# design.net
KiCad netlist of a schematic drawn in Altium Designer
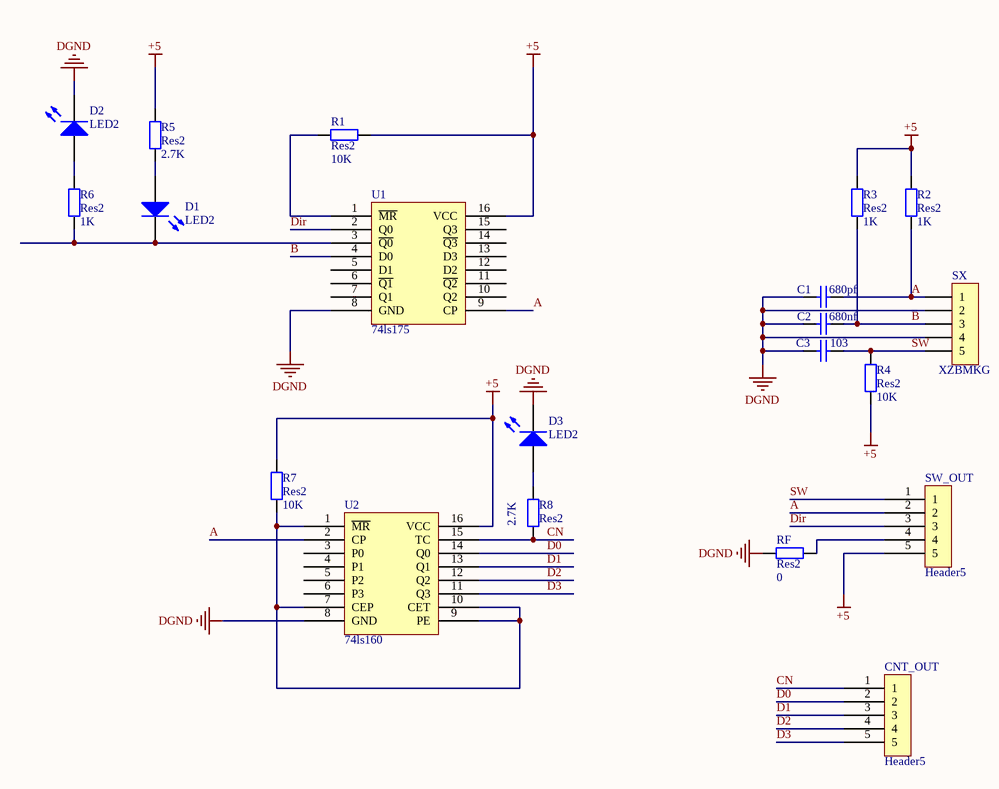
[diagram p0: 正交解码.SchDoc]

(export (version "E")
  (design (tool "Eeschema 10.0.6"))
  (components
    (comp (ref "C1")
      (value "680pf")
      (footprint "0805C")
      (description "Capacitor")
      (fields (field (name "Comment") "104") (field (name "PUBLISHER") "Altium Limited"))
      (libsource (lib "altium-import") (part "root_0_Cap_"))
    )
    (comp (ref "C2")
      (value "680nf")
      (footprint "0805C")
      (description "Capacitor")
      (fields (field (name "Comment") "104") (field (name "PUBLISHER") "Altium Limited"))
      (libsource (lib "altium-import") (part "root_0_Cap_"))
    )
    (comp (ref "C3")
      (value "103")
      (footprint "0805C")
      (description "Capacitor")
      (fields (field (name "Comment") "104") (field (name "PUBLISHER") "Altium Limited"))
      (libsource (lib "altium-import") (part "root_0_Cap_"))
    )
    (comp (ref "CNT_OUT") (value "Header5") (footprint "HDR1X5") (libsource (lib "GDT") (part "Header5")))
    (comp (ref "D1")
      (value "LED2")
      (footprint "LED_0805")
      (description "Typical RED, GREEN, YELLOW, AMBER GaAs LED")
      (fields (field (name "PUBLISHER") "Altium Limited"))
      (libsource (lib "Miscellaneous Devices") (part "LED2"))
    )
    (comp (ref "D2")
      (value "LED2")
      (footprint "LED_0805")
      (description "Typical RED, GREEN, YELLOW, AMBER GaAs LED")
      (fields (field (name "PUBLISHER") "Altium Limited"))
      (libsource (lib "Miscellaneous Devices") (part "LED2"))
    )
    (comp (ref "D3")
      (value "LED2")
      (footprint "LED_0805")
      (description "Typical RED, GREEN, YELLOW, AMBER GaAs LED")
      (fields (field (name "PUBLISHER") "Altium Limited"))
      (libsource (lib "Miscellaneous Devices") (part "LED2"))
    )
    (comp (ref "R1")
      (value "Res2")
      (footprint "0805")
      (description "Resistor")
      (fields (field (name "ALTIUM_VALUE") "10K") (field (name "PUBLISHER") "Altium Limited"))
      (libsource (lib "") (part "Res2_2"))
    )
    (comp (ref "R2")
      (value "Res2")
      (footprint "0805")
      (description "Resistor")
      (fields (field (name "ALTIUM_VALUE") "1K") (field (name "PUBLISHER") "Altium Limited"))
      (libsource (lib "") (part "Res2_1"))
    )
    (comp (ref "R3")
      (value "Res2")
      (footprint "0805")
      (description "Resistor")
      (fields (field (name "ALTIUM_VALUE") "1K") (field (name "PUBLISHER") "Altium Limited"))
      (libsource (lib "") (part "Res2_1"))
    )
    (comp (ref "R4")
      (value "Res2")
      (footprint "0805")
      (description "Resistor")
      (fields (field (name "ALTIUM_VALUE") "10K") (field (name "PUBLISHER") "Altium Limited"))
      (libsource (lib "") (part "Res2_1"))
    )
    (comp (ref "R5")
      (value "Res2")
      (footprint "0805")
      (description "Resistor")
      (fields (field (name "ALTIUM_VALUE") "2.7K") (field (name "PUBLISHER") "Altium Limited"))
      (libsource (lib "Miscellaneous Devices") (part "Res2"))
    )
    (comp (ref "R6")
      (value "Res2")
      (footprint "0805")
      (description "Resistor")
      (fields (field (name "ALTIUM_VALUE") "1K") (field (name "PUBLISHER") "Altium Limited"))
      (libsource (lib "") (part "Res2_1"))
    )
    (comp (ref "R7")
      (value "Res2")
      (footprint "0805")
      (description "Resistor")
      (fields (field (name "ALTIUM_VALUE") "10K") (field (name "PUBLISHER") "Altium Limited"))
      (libsource (lib "") (part "Res2_1"))
    )
    (comp (ref "R8")
      (value "Res2")
      (footprint "0805")
      (description "Resistor")
      (fields (field (name "ALTIUM_VALUE") "2.7K") (field (name "PUBLISHER") "Altium Limited"))
      (libsource (lib "") (part "Res2_1"))
    )
    (comp (ref "RF")
      (value "Res2")
      (footprint "0805")
      (description "Resistor")
      (fields (field (name "ALTIUM_VALUE") "0") (field (name "PUBLISHER") "Altium Limited"))
      (libsource (lib "") (part "Res2_3"))
    )
    (comp (ref "SW_OUT") (value "Header5") (footprint "HDR1X5") (libsource (lib "GDT") (part "Header5")))
    (comp (ref "SX")
      (value "XZBMKG")
      (footprint "EC11")
      (description "Connector")
      (libsource (lib "altium-import") (part "root_0_CON5_"))
    )
    (comp (ref "U1") (value "74ls175") (footprint "DIP16") (libsource (lib "74ls") (part "74ls165")))
    (comp (ref "U2") (value "74ls160") (footprint "DIP16") (libsource (lib "74ls") (part "74ls160")))
  )
  (nets
    (net (code "1") (name "+5") (class "Default")
      (node (ref "R1") (pin "1") (pinfunction "1_1") (pintype "passive"))
      (node (ref "R2") (pin "1") (pinfunction "1_1") (pintype "passive"))
      (node (ref "R3") (pin "1") (pinfunction "1_1") (pintype "passive"))
      (node (ref "R4") (pin "2") (pinfunction "2_2") (pintype "passive"))
      (node (ref "R5") (pin "2") (pinfunction "2_2") (pintype "passive"))
      (node (ref "R7") (pin "1") (pinfunction "1_1") (pintype "passive"))
      (node (ref "SW_OUT") (pin "5") (pinfunction "5_5") (pintype "passive"))
      (node (ref "U1") (pin "16") (pinfunction "VCC_16") (pintype "passive"))
      (node (ref "U2") (pin "16") (pinfunction "VCC_16") (pintype "passive"))
    )
    (net (code "2") (name "/A") (class "Default")
      (node (ref "C1") (pin "2") (pinfunction "2_2") (pintype "passive"))
      (node (ref "R2") (pin "2") (pinfunction "2_2") (pintype "passive"))
      (node (ref "SW_OUT") (pin "2") (pinfunction "2_2") (pintype "passive"))
      (node (ref "SX") (pin "1") (pinfunction "1_1") (pintype "passive"))
      (node (ref "U1") (pin "9") (pinfunction "CP_9") (pintype "passive"))
      (node (ref "U2") (pin "2") (pinfunction "CP_2") (pintype "passive"))
    )
    (net (code "3") (name "/B") (class "Default")
      (node (ref "C2") (pin "2") (pinfunction "2_2") (pintype "passive"))
      (node (ref "R3") (pin "2") (pinfunction "2_2") (pintype "passive"))
      (node (ref "SX") (pin "3") (pinfunction "3_3") (pintype "passive"))
      (node (ref "U1") (pin "4") (pinfunction "D0_4") (pintype "passive"))
    )
    (net (code "4") (name "/CN") (class "Default")
      (node (ref "CNT_OUT") (pin "1") (pinfunction "1_1") (pintype "passive"))
      (node (ref "R8") (pin "2") (pinfunction "2_2") (pintype "passive"))
      (node (ref "U2") (pin "15") (pinfunction "TC_15") (pintype "passive"))
    )
    (net (code "5") (name "/D0") (class "Default")
      (node (ref "CNT_OUT") (pin "2") (pinfunction "2_2") (pintype "passive"))
      (node (ref "U2") (pin "14") (pinfunction "Q0_14") (pintype "passive"))
    )
    (net (code "6") (name "/D1") (class "Default")
      (node (ref "CNT_OUT") (pin "3") (pinfunction "3_3") (pintype "passive"))
      (node (ref "U2") (pin "13") (pinfunction "Q1_13") (pintype "passive"))
    )
    (net (code "7") (name "/D2") (class "Default")
      (node (ref "CNT_OUT") (pin "4") (pinfunction "4_4") (pintype "passive"))
      (node (ref "U2") (pin "12") (pinfunction "Q2_12") (pintype "passive"))
    )
    (net (code "8") (name "/D3") (class "Default")
      (node (ref "CNT_OUT") (pin "5") (pinfunction "5_5") (pintype "passive"))
      (node (ref "U2") (pin "11") (pinfunction "Q3_11") (pintype "passive"))
    )
    (net (code "9") (name "/Dir") (class "Default")
      (node (ref "SW_OUT") (pin "3") (pinfunction "3_3") (pintype "passive"))
      (node (ref "U1") (pin "2") (pinfunction "Q0_2") (pintype "passive"))
    )
    (net (code "10") (name "/SW") (class "Default")
      (node (ref "C3") (pin "2") (pinfunction "2_2") (pintype "passive"))
      (node (ref "R4") (pin "1") (pinfunction "1_1") (pintype "passive"))
      (node (ref "SW_OUT") (pin "1") (pinfunction "1_1") (pintype "passive"))
      (node (ref "SX") (pin "5") (pinfunction "5_5") (pintype "passive"))
    )
    (net (code "11") (name "DGND") (class "Default")
      (node (ref "C1") (pin "1") (pinfunction "1_1") (pintype "passive"))
      (node (ref "C2") (pin "1") (pinfunction "1_1") (pintype "passive"))
      (node (ref "C3") (pin "1") (pinfunction "1_1") (pintype "passive"))
      (node (ref "D2") (pin "2") (pinfunction "K_2") (pintype "passive"))
      (node (ref "D3") (pin "2") (pinfunction "K_2") (pintype "passive"))
      (node (ref "RF") (pin "1") (pinfunction "1_1") (pintype "passive"))
      (node (ref "SX") (pin "2") (pinfunction "2_2") (pintype "passive"))
      (node (ref "SX") (pin "4") (pinfunction "4_4") (pintype "passive"))
      (node (ref "U1") (pin "8") (pinfunction "GND_8") (pintype "passive"))
      (node (ref "U2") (pin "8") (pinfunction "GND_8") (pintype "passive"))
    )
    (net (code "12") (name "Net-(D1-A)") (class "Default")
      (node (ref "D1") (pin "1") (pinfunction "A_1") (pintype "passive"))
      (node (ref "R5") (pin "1") (pinfunction "1_1") (pintype "passive"))
    )
    (net (code "13") (name "Net-(D1-K)") (class "Default")
      (node (ref "D1") (pin "2") (pinfunction "K_2") (pintype "passive"))
      (node (ref "R6") (pin "2") (pinfunction "2_2") (pintype "passive"))
      (node (ref "U1") (pin "3") (pinfunction "~{Q0}_3") (pintype "passive"))
    )
    (net (code "14") (name "Net-(D2-A)") (class "Default")
      (node (ref "D2") (pin "1") (pinfunction "A_1") (pintype "passive"))
      (node (ref "R6") (pin "1") (pinfunction "1_1") (pintype "passive"))
    )
    (net (code "15") (name "Net-(D3-A)") (class "Default")
      (node (ref "D3") (pin "1") (pinfunction "A_1") (pintype "passive"))
      (node (ref "R8") (pin "1") (pinfunction "1_1") (pintype "passive"))
    )
    (net (code "16") (name "Net-(RF-Pad2)") (class "Default")
      (node (ref "RF") (pin "2") (pinfunction "2_2") (pintype "passive"))
      (node (ref "SW_OUT") (pin "4") (pinfunction "4_4") (pintype "passive"))
    )
    (net (code "17") (name "Net-(U1-~{MR})") (class "Default")
      (node (ref "R1") (pin "2") (pinfunction "2_2") (pintype "passive"))
      (node (ref "U1") (pin "1") (pinfunction "~{MR}_1") (pintype "passive"))
    )
    (net (code "18") (name "Net-(U2-CEP)") (class "Default")
      (node (ref "R7") (pin "2") (pinfunction "2_2") (pintype "passive"))
      (node (ref "U2") (pin "1") (pinfunction "~{MR}_1") (pintype "passive"))
      (node (ref "U2") (pin "10") (pinfunction "CET_10") (pintype "passive"))
      (node (ref "U2") (pin "7") (pinfunction "CEP_7") (pintype "passive"))
      (node (ref "U2") (pin "9") (pinfunction "PE_9") (pintype "passive"))
    )
    (net (code "19") (name "unconnected-(U1-D1-Pad5)") (class "Default")
      (node (ref "U1") (pin "5") (pinfunction "D1_5") (pintype "passive"))
    )
    (net (code "20") (name "unconnected-(U1-D2-Pad12)") (class "Default")
      (node (ref "U1") (pin "12") (pinfunction "D2_12") (pintype "passive"))
    )
    (net (code "21") (name "unconnected-(U1-D3-Pad13)") (class "Default")
      (node (ref "U1") (pin "13") (pinfunction "D3_13") (pintype "passive"))
    )
    (net (code "22") (name "unconnected-(U1-Q1-Pad7)") (class "Default")
      (node (ref "U1") (pin "7") (pinfunction "Q1_7") (pintype "passive"))
    )
    (net (code "23") (name "unconnected-(U1-Q2-Pad10)") (class "Default")
      (node (ref "U1") (pin "10") (pinfunction "Q2_10") (pintype "passive"))
    )
    (net (code "24") (name "unconnected-(U1-Q3-Pad15)") (class "Default")
      (node (ref "U1") (pin "15") (pinfunction "Q3_15") (pintype "passive"))
    )
    (net (code "25") (name "unconnected-(U1-~{Q1}-Pad6)") (class "Default")
      (node (ref "U1") (pin "6") (pinfunction "~{Q1}_6") (pintype "passive"))
    )
    (net (code "26") (name "unconnected-(U1-~{Q2}-Pad11)") (class "Default")
      (node (ref "U1") (pin "11") (pinfunction "~{Q2}_11") (pintype "passive"))
    )
    (net (code "27") (name "unconnected-(U1-~{Q3}-Pad14)") (class "Default")
      (node (ref "U1") (pin "14") (pinfunction "~{Q3}_14") (pintype "passive"))
    )
    (net (code "28") (name "unconnected-(U2-P0-Pad3)") (class "Default")
      (node (ref "U2") (pin "3") (pinfunction "P0_3") (pintype "passive"))
    )
    (net (code "29") (name "unconnected-(U2-P1-Pad4)") (class "Default")
      (node (ref "U2") (pin "4") (pinfunction "P1_4") (pintype "passive"))
    )
    (net (code "30") (name "unconnected-(U2-P2-Pad5)") (class "Default")
      (node (ref "U2") (pin "5") (pinfunction "P2_5") (pintype "passive"))
    )
    (net (code "31") (name "unconnected-(U2-P3-Pad6)") (class "Default")
      (node (ref "U2") (pin "6") (pinfunction "P3_6") (pintype "passive"))
    )
  )
)
